# PMS.net
KiCad netlist of a schematic drawn in EAGLE
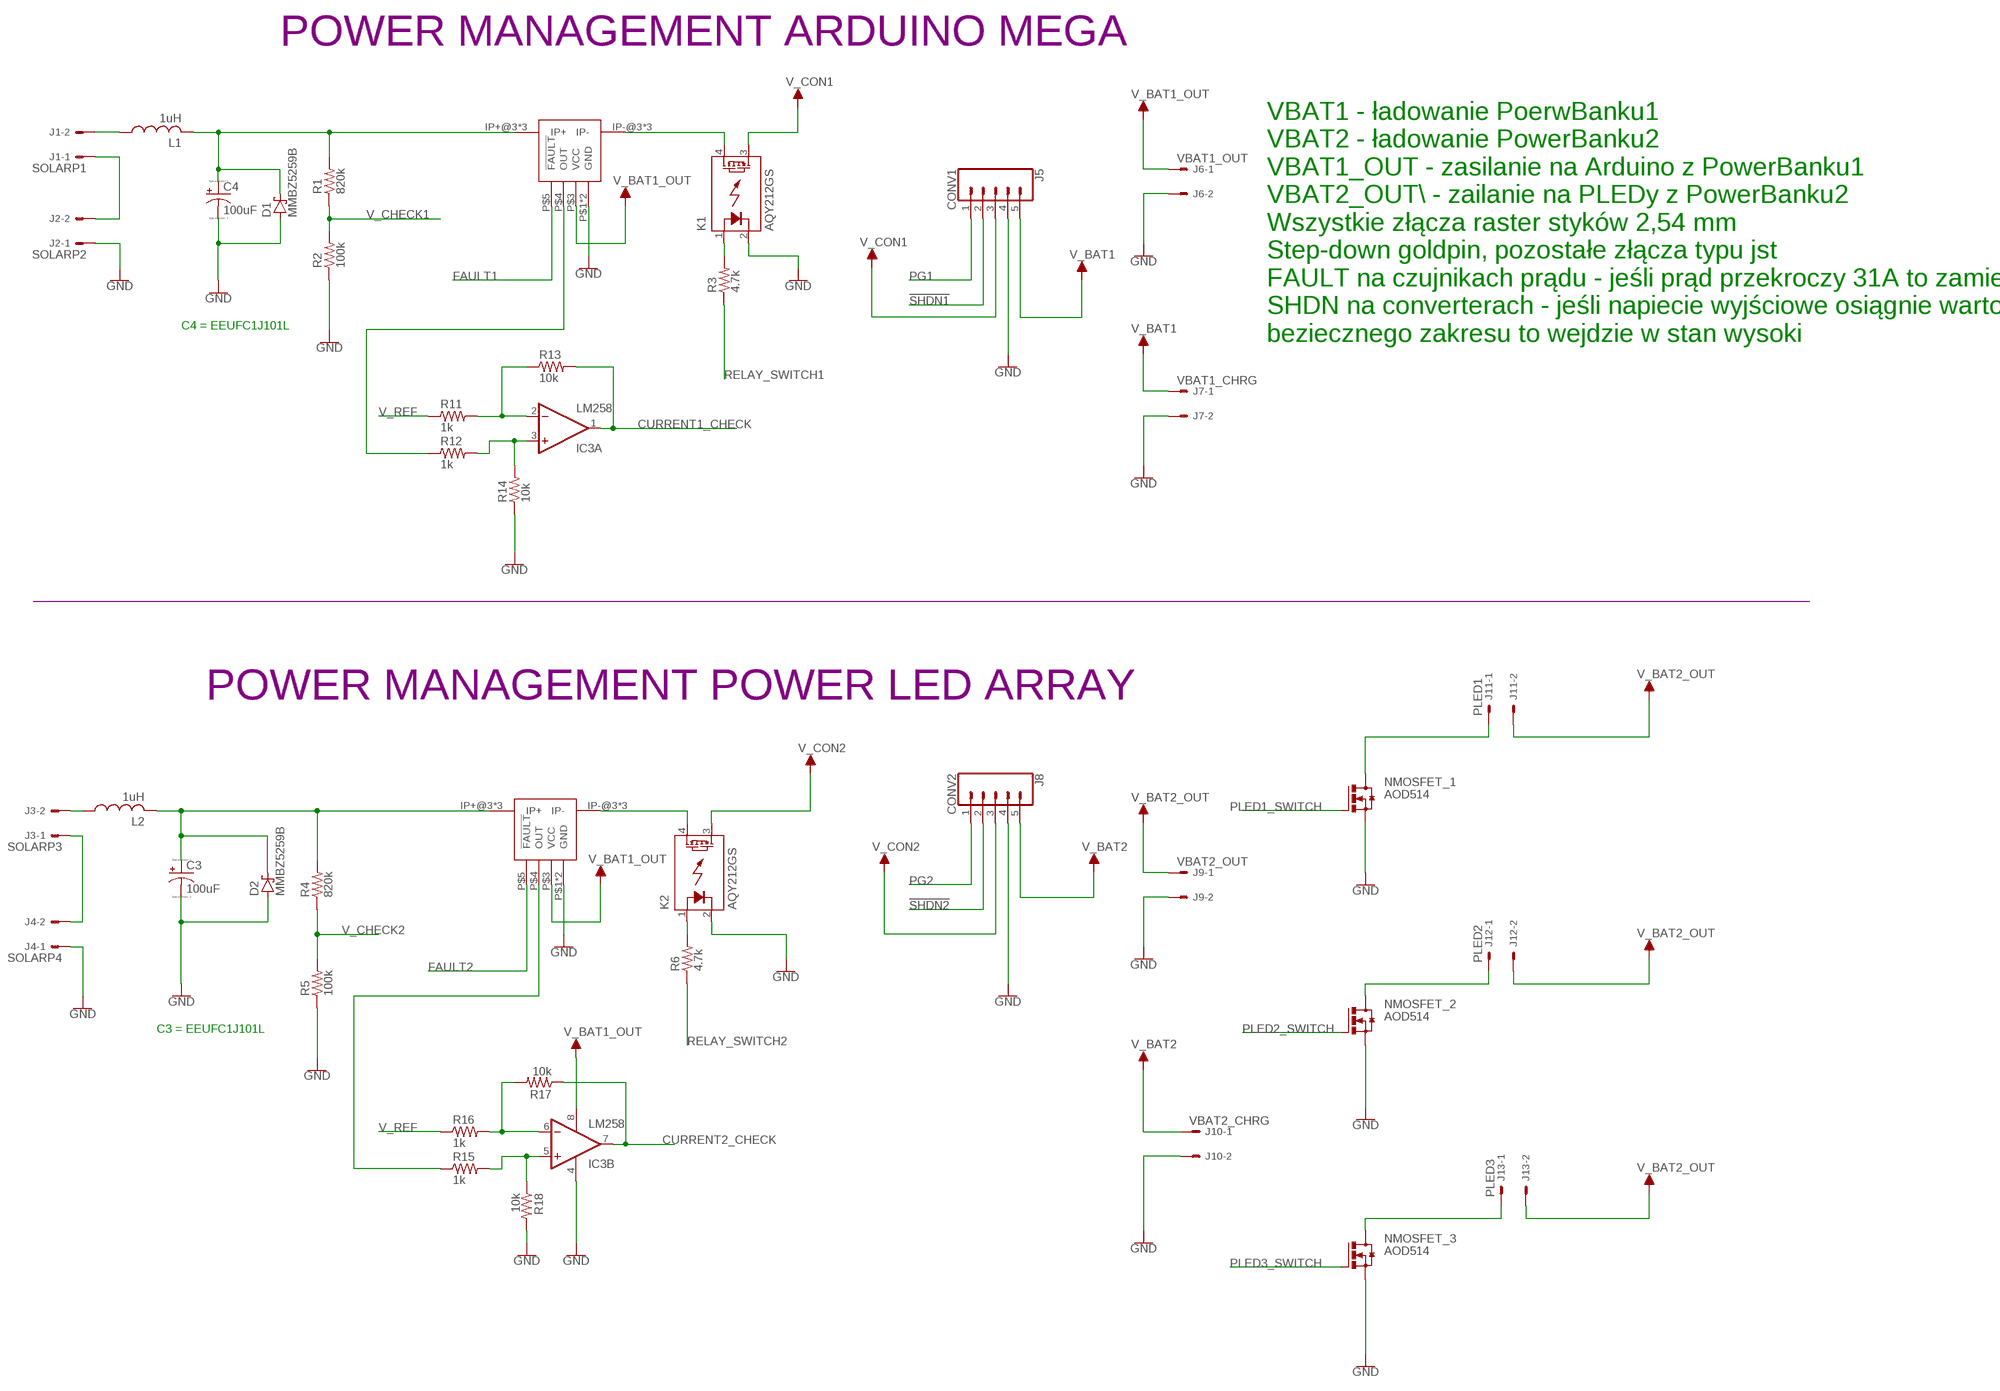
[diagram p0: schematic, sheet 1, part 1 of 2]
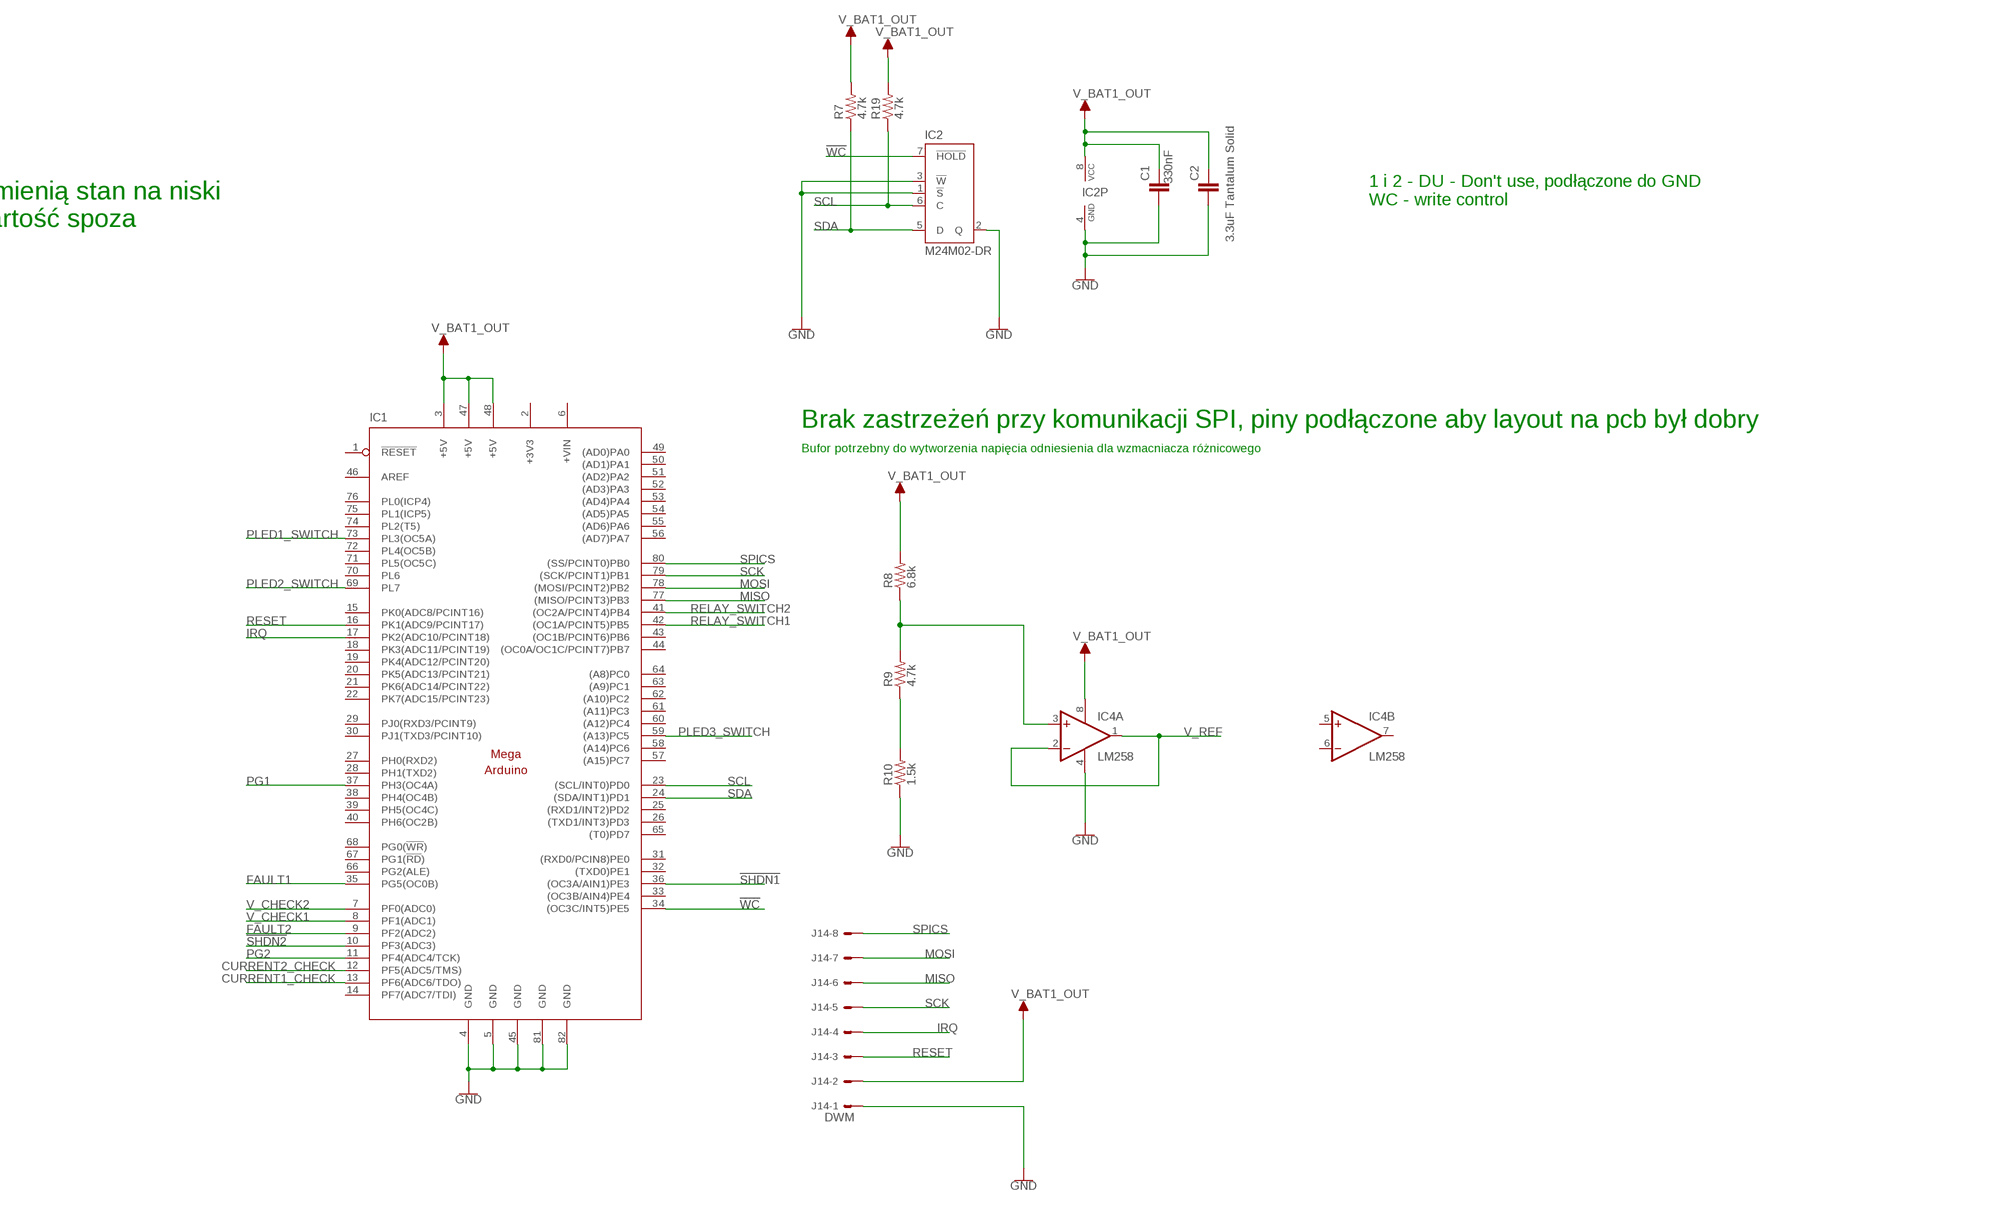
[diagram p1: schematic, sheet 1, part 2 of 2]

(export (version "E")
  (design (tool "Eeschema 10.0.6"))
  (components
    (comp (ref "C1")
      (value "330nF")
      (footprint "eagle-import:C0805")
      (libsource (lib "eagle-import") (part "C-EUC0805"))
    )
    (comp (ref "C2")
      (value "3.3uF Tantalum Solid")
      (footprint "eagle-import:C1206")
      (libsource (lib "eagle-import") (part "C-EUC1206"))
    )
    (comp (ref "C3")
      (value "100uF")
      (footprint "eagle-import:E3,5-8")
      (libsource (lib "eagle-import") (part "CPOL-USE3.5-8"))
    )
    (comp (ref "C4")
      (value "100uF")
      (footprint "eagle-import:E3,5-8")
      (libsource (lib "eagle-import") (part "CPOL-USE3.5-8"))
    )
    (comp (ref "CURRETN_SENS")
      (value "ACS711EXSH")
      (footprint "eagle-import:POLOLU2453_SMALL_HOLES")
      (libsource (lib "eagle-import") (part "ACS711EXSH"))
    )
    (comp (ref "D1")
      (value "MMBZ5259B")
      (footprint "eagle-import:SOT23")
      (libsource (lib "eagle-import") (part "BAS40"))
    )
    (comp (ref "D2")
      (value "MMBZ5259B")
      (footprint "eagle-import:SOT23")
      (libsource (lib "eagle-import") (part "BAS40"))
    )
    (comp (ref "IC1")
      (value "MEGAARDUINO_13")
      (footprint "eagle-import:MEGA_ARDUINO_3")
      (libsource (lib "eagle-import") (part "MEGAARDUINO_13"))
    )
    (comp (ref "IC2")
      (value "M24M02-DR")
      (footprint "eagle-import:SO08")
      (libsource (lib "eagle-import") (part "ST95P08M"))
    )
    (comp (ref "IC3")
      (value "LM258")
      (footprint "eagle-import:SO08")
      (libsource (lib "eagle-import") (part "LM358D"))
    )
    (comp (ref "IC4")
      (value "LM258")
      (footprint "eagle-import:SO08")
      (libsource (lib "eagle-import") (part "LM358D"))
    )
    (comp (ref "J1")
      (value "SOLARP1")
      (footprint "eagle-import:6410-02")
      (libsource (lib "eagle-import") (part "22-?-0227-2021"))
    )
    (comp (ref "J2")
      (value "SOLARP2")
      (footprint "eagle-import:6410-02")
      (libsource (lib "eagle-import") (part "22-?-0227-2021"))
    )
    (comp (ref "J3")
      (value "SOLARP3")
      (footprint "eagle-import:6410-02")
      (libsource (lib "eagle-import") (part "22-?-0227-2021"))
    )
    (comp (ref "J4")
      (value "SOLARP4")
      (footprint "eagle-import:6410-02")
      (libsource (lib "eagle-import") (part "22-?-0227-2021"))
    )
    (comp (ref "J5")
      (value "CONV1")
      (footprint "eagle-import:1X05")
      (libsource (lib "eagle-import") (part "CONN_05"))
    )
    (comp (ref "J6")
      (value "VBAT1_OUT")
      (footprint "eagle-import:6410-02")
      (libsource (lib "eagle-import") (part "22-?-0227-2021"))
    )
    (comp (ref "J7")
      (value "VBAT1_CHRG")
      (footprint "eagle-import:6410-02")
      (libsource (lib "eagle-import") (part "22-?-0227-2021"))
    )
    (comp (ref "J8")
      (value "CONV2")
      (footprint "eagle-import:1X05")
      (libsource (lib "eagle-import") (part "CONN_05"))
    )
    (comp (ref "J9")
      (value "VBAT2_OUT")
      (footprint "eagle-import:6410-02")
      (libsource (lib "eagle-import") (part "22-?-0227-2021"))
    )
    (comp (ref "J10")
      (value "VBAT2_CHRG")
      (footprint "eagle-import:6410-02")
      (libsource (lib "eagle-import") (part "22-?-0227-2021"))
    )
    (comp (ref "J11")
      (value "PLED1")
      (footprint "eagle-import:6410-02")
      (libsource (lib "eagle-import") (part "22-?-0227-2021"))
    )
    (comp (ref "J12")
      (value "PLED2")
      (footprint "eagle-import:6410-02")
      (libsource (lib "eagle-import") (part "22-?-0227-2021"))
    )
    (comp (ref "J13")
      (value "PLED3")
      (footprint "eagle-import:6410-02")
      (libsource (lib "eagle-import") (part "22-?-0227-2021"))
    )
    (comp (ref "J14")
      (value "DWM")
      (footprint "eagle-import:6410-08")
      (libsource (lib "eagle-import") (part "22-?-0827-2081"))
    )
    (comp (ref "K1")
      (value "AQY212GS")
      (footprint "eagle-import:SOP04")
      (libsource (lib "eagle-import") (part "AQYSOP21"))
    )
    (comp (ref "K2")
      (value "AQY212GS")
      (footprint "eagle-import:SOP04")
      (libsource (lib "eagle-import") (part "AQYSOP21"))
    )
    (comp (ref "L1")
      (value "1uH")
      (footprint "eagle-import:L3225M")
      (libsource (lib "eagle-import") (part "L-USL3225M"))
    )
    (comp (ref "L2")
      (value "1uH")
      (footprint "eagle-import:L3225M")
      (libsource (lib "eagle-import") (part "L-USL3225M"))
    )
    (comp (ref "NMOSFET_1")
      (value "AOD514")
      (footprint "eagle-import:TO252")
      (libsource (lib "eagle-import") (part "N_MOSFET_TO252"))
    )
    (comp (ref "NMOSFET_2")
      (value "AOD514")
      (footprint "eagle-import:TO252")
      (libsource (lib "eagle-import") (part "N_MOSFET_TO252"))
    )
    (comp (ref "NMOSFET_3")
      (value "AOD514")
      (footprint "eagle-import:TO252")
      (libsource (lib "eagle-import") (part "N_MOSFET_TO252"))
    )
    (comp (ref "R1")
      (value "820k")
      (footprint "eagle-import:R0805")
      (libsource (lib "eagle-import") (part "R-US_R0805"))
    )
    (comp (ref "R2")
      (value "100k")
      (footprint "eagle-import:R0805")
      (libsource (lib "eagle-import") (part "R-US_R0805"))
    )
    (comp (ref "R3")
      (value "4.7k")
      (footprint "eagle-import:R0805")
      (libsource (lib "eagle-import") (part "R-US_R0805"))
    )
    (comp (ref "R4")
      (value "820k")
      (footprint "eagle-import:R0805")
      (libsource (lib "eagle-import") (part "R-US_R0805"))
    )
    (comp (ref "R5")
      (value "100k")
      (footprint "eagle-import:R0805")
      (libsource (lib "eagle-import") (part "R-US_R0805"))
    )
    (comp (ref "R6")
      (value "4.7k")
      (footprint "eagle-import:R0805")
      (libsource (lib "eagle-import") (part "R-US_R0805"))
    )
    (comp (ref "R7")
      (value "4.7k")
      (footprint "eagle-import:R0805")
      (libsource (lib "eagle-import") (part "R-US_R0805"))
    )
    (comp (ref "R8")
      (value "6.8k")
      (footprint "eagle-import:R0805")
      (libsource (lib "eagle-import") (part "R-US_R0805"))
    )
    (comp (ref "R9")
      (value "4.7k")
      (footprint "eagle-import:R0805")
      (libsource (lib "eagle-import") (part "R-US_R0805"))
    )
    (comp (ref "R10")
      (value "1.5k")
      (footprint "eagle-import:R0805")
      (libsource (lib "eagle-import") (part "R-US_R0805"))
    )
    (comp (ref "R11")
      (value "1k")
      (footprint "eagle-import:R0805")
      (libsource (lib "eagle-import") (part "R-US_R0805"))
    )
    (comp (ref "R12")
      (value "1k")
      (footprint "eagle-import:R0805")
      (libsource (lib "eagle-import") (part "R-US_R0805"))
    )
    (comp (ref "R13")
      (value "10k")
      (footprint "eagle-import:R0805")
      (libsource (lib "eagle-import") (part "R-US_R0805"))
    )
    (comp (ref "R14")
      (value "10k")
      (footprint "eagle-import:R0805")
      (libsource (lib "eagle-import") (part "R-US_R0805"))
    )
    (comp (ref "R15")
      (value "1k")
      (footprint "eagle-import:R0805")
      (libsource (lib "eagle-import") (part "R-US_R0805"))
    )
    (comp (ref "R16")
      (value "1k")
      (footprint "eagle-import:R0805")
      (libsource (lib "eagle-import") (part "R-US_R0805"))
    )
    (comp (ref "R17")
      (value "10k")
      (footprint "eagle-import:R0805")
      (libsource (lib "eagle-import") (part "R-US_R0805"))
    )
    (comp (ref "R18")
      (value "10k")
      (footprint "eagle-import:R0805")
      (libsource (lib "eagle-import") (part "R-US_R0805"))
    )
    (comp (ref "R19")
      (value "4.7k")
      (footprint "eagle-import:R0805")
      (libsource (lib "eagle-import") (part "R-US_R0805"))
    )
    (comp (ref "U$2")
      (value "ACS711EXSH")
      (footprint "eagle-import:POLOLU2453_SMALL_HOLES")
      (libsource (lib "eagle-import") (part "ACS711EXSH"))
    )
  )
  (nets
    (net (code "1") (name "/+3V3") (class "Default")
      (node (ref "IC1") (pin "2") (pinfunction "+3V3_2") (pintype "power_in"))
    )
    (net (code "2") (name "/+VIN") (class "Default")
      (node (ref "IC1") (pin "6") (pinfunction "+VIN_6") (pintype "power_in"))
    )
    (net (code "3") (name "/CURRENT1_CHECK") (class "Default")
      (node (ref "IC1") (pin "13") (pinfunction "PF6(ADC6/TDO)_13") (pintype "bidirectional"))
      (node (ref "IC3") (pin "1") (pinfunction "OUT_1") (pintype "output"))
      (node (ref "R13") (pin "2") (pinfunction "2_2") (pintype "passive"))
    )
    (net (code "4") (name "/CURRENT2_CHECK") (class "Default")
      (node (ref "IC1") (pin "12") (pinfunction "PF5(ADC5/TMS)_12") (pintype "bidirectional"))
      (node (ref "IC3") (pin "7") (pinfunction "OUT_7") (pintype "output"))
      (node (ref "R17") (pin "1") (pinfunction "1_1") (pintype "passive"))
    )
    (net (code "5") (name "/FAULT1") (class "Default")
      (node (ref "CURRETN_SENS") (pin "P$5") (pinfunction "~{FAULT}_P$5") (pintype "bidirectional"))
      (node (ref "IC1") (pin "35") (pinfunction "PG5(OC0B)_35") (pintype "bidirectional"))
    )
    (net (code "6") (name "/FAULT2") (class "Default")
      (node (ref "IC1") (pin "9") (pinfunction "PF2(ADC2)_9") (pintype "bidirectional"))
      (node (ref "U$2") (pin "P$5") (pinfunction "~{FAULT}_P$5") (pintype "bidirectional"))
    )
    (net (code "7") (name "/IRQ") (class "Default")
      (node (ref "IC1") (pin "17") (pinfunction "PK2(ADC10/PCINT18)_17") (pintype "bidirectional"))
      (node (ref "J14") (pin "4") (pinfunction "S_4") (pintype "passive"))
    )
    (net (code "8") (name "/MISO") (class "Default")
      (node (ref "IC1") (pin "77") (pinfunction "(MISO/PCINT3)PB3_77") (pintype "bidirectional"))
      (node (ref "J14") (pin "6") (pinfunction "S_6") (pintype "passive"))
    )
    (net (code "9") (name "/MOSI") (class "Default")
      (node (ref "IC1") (pin "78") (pinfunction "(MOSI/PCINT2)PB2_78") (pintype "bidirectional"))
      (node (ref "J14") (pin "7") (pinfunction "S_7") (pintype "passive"))
    )
    (net (code "10") (name "/PG1") (class "Default")
      (node (ref "IC1") (pin "37") (pinfunction "PH3(OC4A)_37") (pintype "bidirectional"))
      (node (ref "J5") (pin "1") (pinfunction "1_1") (pintype "passive"))
    )
    (net (code "11") (name "/PG2") (class "Default")
      (node (ref "IC1") (pin "11") (pinfunction "PF4(ADC4/TCK)_11") (pintype "bidirectional"))
      (node (ref "J8") (pin "1") (pinfunction "1_1") (pintype "passive"))
    )
    (net (code "12") (name "/PLED1_SWITCH") (class "Default")
      (node (ref "IC1") (pin "73") (pinfunction "PL3(OC5A)_73") (pintype "bidirectional"))
      (node (ref "NMOSFET_1") (pin "1") (pinfunction "G_1") (pintype "passive"))
    )
    (net (code "13") (name "/PLED2_SWITCH") (class "Default")
      (node (ref "IC1") (pin "69") (pinfunction "PL7_69") (pintype "bidirectional"))
      (node (ref "NMOSFET_2") (pin "1") (pinfunction "G_1") (pintype "passive"))
    )
    (net (code "14") (name "/PLED3_SWITCH") (class "Default")
      (node (ref "IC1") (pin "59") (pinfunction "(A13)PC5_59") (pintype "bidirectional"))
      (node (ref "NMOSFET_3") (pin "1") (pinfunction "G_1") (pintype "passive"))
    )
    (net (code "15") (name "/RELAY_SWITCH1") (class "Default")
      (node (ref "IC1") (pin "42") (pinfunction "(OC1A/PCINT5)PB5_42") (pintype "bidirectional"))
      (node (ref "R3") (pin "1") (pinfunction "1_1") (pintype "passive"))
    )
    (net (code "16") (name "/RELAY_SWITCH2") (class "Default")
      (node (ref "IC1") (pin "41") (pinfunction "(OC2A/PCINT4)PB4_41") (pintype "bidirectional"))
      (node (ref "R6") (pin "1") (pinfunction "1_1") (pintype "passive"))
    )
    (net (code "17") (name "/RESET") (class "Default")
      (node (ref "IC1") (pin "16") (pinfunction "PK1(ADC9/PCINT17)_16") (pintype "bidirectional"))
      (node (ref "J14") (pin "3") (pinfunction "S_3") (pintype "passive"))
    )
    (net (code "18") (name "/SCK") (class "Default")
      (node (ref "IC1") (pin "79") (pinfunction "(SCK/PCINT1)PB1_79") (pintype "bidirectional"))
      (node (ref "J14") (pin "5") (pinfunction "S_5") (pintype "passive"))
    )
    (net (code "19") (name "/SCL") (class "Default")
      (node (ref "IC1") (pin "23") (pinfunction "(SCL/INT0)PD0_23") (pintype "bidirectional"))
      (node (ref "IC2") (pin "6") (pinfunction "C_6") (pintype "input"))
      (node (ref "R19") (pin "1") (pinfunction "1_1") (pintype "passive"))
    )
    (net (code "20") (name "/SDA") (class "Default")
      (node (ref "IC1") (pin "24") (pinfunction "(SDA/INT1)PD1_24") (pintype "bidirectional"))
      (node (ref "IC2") (pin "5") (pinfunction "D_5") (pintype "input"))
      (node (ref "R7") (pin "1") (pinfunction "1_1") (pintype "passive"))
    )
    (net (code "21") (name "/SPICS") (class "Default")
      (node (ref "IC1") (pin "80") (pinfunction "(SS/PCINT0)PB0_80") (pintype "bidirectional"))
      (node (ref "J14") (pin "8") (pinfunction "S_8") (pintype "passive"))
    )
    (net (code "22") (name "/V_CHECK1") (class "Default")
      (node (ref "IC1") (pin "8") (pinfunction "PF1(ADC1)_8") (pintype "bidirectional"))
      (node (ref "R1") (pin "1") (pinfunction "1_1") (pintype "passive"))
      (node (ref "R2") (pin "2") (pinfunction "2_2") (pintype "passive"))
    )
    (net (code "23") (name "/V_CHECK2") (class "Default")
      (node (ref "IC1") (pin "7") (pinfunction "PF0(ADC0)_7") (pintype "bidirectional"))
      (node (ref "R4") (pin "1") (pinfunction "1_1") (pintype "passive"))
      (node (ref "R5") (pin "2") (pinfunction "2_2") (pintype "passive"))
    )
    (net (code "24") (name "/V_REF") (class "Default")
      (node (ref "IC4") (pin "1") (pinfunction "OUT_1") (pintype "output"))
      (node (ref "IC4") (pin "2") (pinfunction "-IN_2") (pintype "input"))
      (node (ref "R11") (pin "1") (pinfunction "1_1") (pintype "passive"))
      (node (ref "R16") (pin "1") (pinfunction "1_1") (pintype "passive"))
    )
    (net (code "25") (name "/~{SHDN1}") (class "Default")
      (node (ref "IC1") (pin "36") (pinfunction "(OC3A/AIN1)PE3_36") (pintype "bidirectional"))
      (node (ref "J5") (pin "2") (pinfunction "2_2") (pintype "passive"))
    )
    (net (code "26") (name "/~{SHDN2}") (class "Default")
      (node (ref "IC1") (pin "10") (pinfunction "PF3(ADC3)_10") (pintype "bidirectional"))
      (node (ref "J8") (pin "2") (pinfunction "2_2") (pintype "passive"))
    )
    (net (code "27") (name "/~{WC}") (class "Default")
      (node (ref "IC1") (pin "34") (pinfunction "(OC3C/INT5)PE5_34") (pintype "bidirectional"))
      (node (ref "IC2") (pin "7") (pinfunction "~{HOLD}_7") (pintype "input"))
    )
    (net (code "28") (name "GND") (class "Default")
      (node (ref "C1") (pin "1") (pinfunction "1_1") (pintype "passive"))
      (node (ref "C2") (pin "1") (pinfunction "1_1") (pintype "passive"))
      (node (ref "C3") (pin "-") (pinfunction "-_-") (pintype "passive"))
      (node (ref "C4") (pin "-") (pinfunction "-_-") (pintype "passive"))
      (node (ref "CURRETN_SENS") (pin "P$1") (pinfunction "GND_P$1") (pintype "bidirectional"))
      (node (ref "CURRETN_SENS") (pin "P$2") (pinfunction "GND_P$2") (pintype "bidirectional"))
      (node (ref "D1") (pin "1") (pinfunction "A_1") (pintype "passive"))
      (node (ref "D2") (pin "1") (pinfunction "A_1") (pintype "passive"))
      (node (ref "IC1") (pin "4") (pinfunction "GND_4") (pintype "power_in"))
      (node (ref "IC1") (pin "45") (pinfunction "GND_45") (pintype "power_in"))
      (node (ref "IC1") (pin "5") (pinfunction "GND_5") (pintype "power_in"))
      (node (ref "IC1") (pin "81") (pinfunction "GND_81") (pintype "power_in"))
      (node (ref "IC1") (pin "82") (pinfunction "GND_82") (pintype "power_in"))
      (node (ref "IC2") (pin "1") (pinfunction "~{S}_1") (pintype "input"))
      (node (ref "IC2") (pin "2") (pinfunction "Q_2") (pintype "tri_state"))
      (node (ref "IC2") (pin "3") (pinfunction "~{W}_3") (pintype "input"))
      (node (ref "IC2") (pin "4") (pinfunction "GND_4") (pintype "power_in"))
      (node (ref "IC3") (pin "4") (pinfunction "V-_4") (pintype "power_in"))
      (node (ref "IC4") (pin "4") (pinfunction "V-_4") (pintype "power_in"))
      (node (ref "J10") (pin "2") (pinfunction "S_2") (pintype "passive"))
      (node (ref "J14") (pin "1") (pinfunction "S_1") (pintype "passive"))
      (node (ref "J2") (pin "1") (pinfunction "S_1") (pintype "passive"))
      (node (ref "J4") (pin "1") (pinfunction "S_1") (pintype "passive"))
      (node (ref "J5") (pin "4") (pinfunction "4_4") (pintype "passive"))
      (node (ref "J6") (pin "2") (pinfunction "S_2") (pintype "passive"))
      (node (ref "J7") (pin "2") (pinfunction "S_2") (pintype "passive"))
      (node (ref "J8") (pin "4") (pinfunction "4_4") (pintype "passive"))
      (node (ref "J9") (pin "2") (pinfunction "S_2") (pintype "passive"))
      (node (ref "K1") (pin "2") (pinfunction "K_2") (pintype "passive"))
      (node (ref "K2") (pin "2") (pinfunction "K_2") (pintype "passive"))
      (node (ref "NMOSFET_1") (pin "3") (pinfunction "S_3") (pintype "passive"))
      (node (ref "NMOSFET_2") (pin "3") (pinfunction "S_3") (pintype "passive"))
      (node (ref "NMOSFET_3") (pin "3") (pinfunction "S_3") (pintype "passive"))
      (node (ref "R10") (pin "1") (pinfunction "1_1") (pintype "passive"))
      (node (ref "R14") (pin "1") (pinfunction "1_1") (pintype "passive"))
      (node (ref "R18") (pin "2") (pinfunction "2_2") (pintype "passive"))
      (node (ref "R2") (pin "1") (pinfunction "1_1") (pintype "passive"))
      (node (ref "R5") (pin "1") (pinfunction "1_1") (pintype "passive"))
      (node (ref "U$2") (pin "P$1") (pinfunction "GND_P$1") (pintype "bidirectional"))
      (node (ref "U$2") (pin "P$2") (pinfunction "GND_P$2") (pintype "bidirectional"))
    )
    (net (code "29") (name "Net-(CURRETN_SENS-OUT)") (class "Default")
      (node (ref "CURRETN_SENS") (pin "P$4") (pinfunction "OUT_P$4") (pintype "bidirectional"))
      (node (ref "R12") (pin "1") (pinfunction "1_1") (pintype "passive"))
    )
    (net (code "30") (name "Net-(D1-C)") (class "Default")
      (node (ref "C4") (pin "+") (pinfunction "+_+") (pintype "passive"))
      (node (ref "CURRETN_SENS") (pin "IP+@3") (pinfunction "IP+_IP+@3") (pintype "bidirectional"))
      (node (ref "CURRETN_SENS") (pin "IP+@4") (pinfunction "IP+_IP+@4") (pintype "bidirectional"))
      (node (ref "CURRETN_SENS") (pin "IP+@5") (pinfunction "IP+_IP+@5") (pintype "bidirectional"))
      (node (ref "D1") (pin "3") (pinfunction "C_3") (pintype "passive"))
      (node (ref "L1") (pin "2") (pinfunction "2_2") (pintype "passive"))
      (node (ref "R1") (pin "2") (pinfunction "2_2") (pintype "passive"))
    )
    (net (code "31") (name "Net-(D2-C)") (class "Default")
      (node (ref "C3") (pin "+") (pinfunction "+_+") (pintype "passive"))
      (node (ref "D2") (pin "3") (pinfunction "C_3") (pintype "passive"))
      (node (ref "L2") (pin "2") (pinfunction "2_2") (pintype "passive"))
      (node (ref "R4") (pin "2") (pinfunction "2_2") (pintype "passive"))
      (node (ref "U$2") (pin "IP+@3") (pinfunction "IP+_IP+@3") (pintype "bidirectional"))
      (node (ref "U$2") (pin "IP+@4") (pinfunction "IP+_IP+@4") (pintype "bidirectional"))
      (node (ref "U$2") (pin "IP+@5") (pinfunction "IP+_IP+@5") (pintype "bidirectional"))
    )
    (net (code "32") (name "Net-(IC3A-+IN)") (class "Default")
      (node (ref "IC3") (pin "3") (pinfunction "+IN_3") (pintype "input"))
      (node (ref "R12") (pin "2") (pinfunction "2_2") (pintype "passive"))
      (node (ref "R14") (pin "2") (pinfunction "2_2") (pintype "passive"))
    )
    (net (code "33") (name "Net-(IC3A--IN)") (class "Default")
      (node (ref "IC3") (pin "2") (pinfunction "-IN_2") (pintype "input"))
      (node (ref "R11") (pin "2") (pinfunction "2_2") (pintype "passive"))
      (node (ref "R13") (pin "1") (pinfunction "1_1") (pintype "passive"))
    )
    (net (code "34") (name "Net-(IC3B-+IN)") (class "Default")
      (node (ref "IC3") (pin "5") (pinfunction "+IN_5") (pintype "input"))
      (node (ref "R15") (pin "2") (pinfunction "2_2") (pintype "passive"))
      (node (ref "R18") (pin "1") (pinfunction "1_1") (pintype "passive"))
    )
    (net (code "35") (name "Net-(IC3B--IN)") (class "Default")
      (node (ref "IC3") (pin "6") (pinfunction "-IN_6") (pintype "input"))
      (node (ref "R16") (pin "2") (pinfunction "2_2") (pintype "passive"))
      (node (ref "R17") (pin "2") (pinfunction "2_2") (pintype "passive"))
    )
    (net (code "36") (name "Net-(IC4A-+IN)") (class "Default")
      (node (ref "IC4") (pin "3") (pinfunction "+IN_3") (pintype "input"))
      (node (ref "R8") (pin "1") (pinfunction "1_1") (pintype "passive"))
      (node (ref "R9") (pin "2") (pinfunction "2_2") (pintype "passive"))
    )
    (net (code "37") (name "Net-(J1A-S)") (class "Default")
      (node (ref "J1") (pin "1") (pinfunction "S_1") (pintype "passive"))
      (node (ref "J2") (pin "2") (pinfunction "S_2") (pintype "passive"))
    )
    (net (code "38") (name "Net-(J1B-S)") (class "Default")
      (node (ref "J1") (pin "2") (pinfunction "S_2") (pintype "passive"))
      (node (ref "L1") (pin "1") (pinfunction "1_1") (pintype "passive"))
    )
    (net (code "39") (name "Net-(J3A-S)") (class "Default")
      (node (ref "J3") (pin "1") (pinfunction "S_1") (pintype "passive"))
      (node (ref "J4") (pin "2") (pinfunction "S_2") (pintype "passive"))
    )
    (net (code "40") (name "Net-(J3B-S)") (class "Default")
      (node (ref "J3") (pin "2") (pinfunction "S_2") (pintype "passive"))
      (node (ref "L2") (pin "1") (pinfunction "1_1") (pintype "passive"))
    )
    (net (code "41") (name "Net-(J11A-S)") (class "Default")
      (node (ref "J11") (pin "1") (pinfunction "S_1") (pintype "passive"))
      (node (ref "NMOSFET_1") (pin "4") (pinfunction "D_4") (pintype "passive"))
    )
    (net (code "42") (name "Net-(J12A-S)") (class "Default")
      (node (ref "J12") (pin "1") (pinfunction "S_1") (pintype "passive"))
      (node (ref "NMOSFET_2") (pin "4") (pinfunction "D_4") (pintype "passive"))
    )
    (net (code "43") (name "Net-(J13A-S)") (class "Default")
      (node (ref "J13") (pin "1") (pinfunction "S_1") (pintype "passive"))
      (node (ref "NMOSFET_3") (pin "4") (pinfunction "D_4") (pintype "passive"))
    )
    (net (code "44") (name "Net-(K1-A)") (class "Default")
      (node (ref "K1") (pin "1") (pinfunction "A_1") (pintype "passive"))
      (node (ref "R3") (pin "2") (pinfunction "2_2") (pintype "passive"))
    )
    (net (code "45") (name "Net-(K1-DS1)") (class "Default")
      (node (ref "CURRETN_SENS") (pin "IP-@3") (pinfunction "IP-_IP-@3") (pintype "bidirectional"))
      (node (ref "CURRETN_SENS") (pin "IP-@4") (pinfunction "IP-_IP-@4") (pintype "bidirectional"))
      (node (ref "CURRETN_SENS") (pin "IP-@5") (pinfunction "IP-_IP-@5") (pintype "bidirectional"))
      (node (ref "K1") (pin "4") (pinfunction "DS1_4") (pintype "passive"))
    )
    (net (code "46") (name "Net-(K2-A)") (class "Default")
      (node (ref "K2") (pin "1") (pinfunction "A_1") (pintype "passive"))
      (node (ref "R6") (pin "2") (pinfunction "2_2") (pintype "passive"))
    )
    (net (code "47") (name "Net-(K2-DS1)") (class "Default")
      (node (ref "K2") (pin "4") (pinfunction "DS1_4") (pintype "passive"))
      (node (ref "U$2") (pin "IP-@3") (pinfunction "IP-_IP-@3") (pintype "bidirectional"))
      (node (ref "U$2") (pin "IP-@4") (pinfunction "IP-_IP-@4") (pintype "bidirectional"))
      (node (ref "U$2") (pin "IP-@5") (pinfunction "IP-_IP-@5") (pintype "bidirectional"))
    )
    (net (code "48") (name "Net-(R10-Pad2)") (class "Default")
      (node (ref "R10") (pin "2") (pinfunction "2_2") (pintype "passive"))
      (node (ref "R9") (pin "1") (pinfunction "1_1") (pintype "passive"))
    )
    (net (code "49") (name "Net-(U$2-OUT)") (class "Default")
      (node (ref "R15") (pin "1") (pinfunction "1_1") (pintype "passive"))
      (node (ref "U$2") (pin "P$4") (pinfunction "OUT_P$4") (pintype "bidirectional"))
    )
    (net (code "50") (name "V_BAT1") (class "Default")
      (node (ref "J5") (pin "5") (pinfunction "5_5") (pintype "passive"))
      (node (ref "J7") (pin "1") (pinfunction "S_1") (pintype "passive"))
    )
    (net (code "51") (name "V_BAT1_OUT") (class "Default")
      (node (ref "C1") (pin "2") (pinfunction "2_2") (pintype "passive"))
      (node (ref "C2") (pin "2") (pinfunction "2_2") (pintype "passive"))
      (node (ref "CURRETN_SENS") (pin "P$3") (pinfunction "VCC_P$3") (pintype "bidirectional"))
      (node (ref "IC1") (pin "3") (pinfunction "+5V_3") (pintype "power_in"))
      (node (ref "IC1") (pin "47") (pinfunction "+5V_47") (pintype "power_in"))
      (node (ref "IC1") (pin "48") (pinfunction "+5V_48") (pintype "power_in"))
      (node (ref "IC2") (pin "8") (pinfunction "VCC_8") (pintype "power_in"))
      (node (ref "IC3") (pin "8") (pinfunction "V+_8") (pintype "power_in"))
      (node (ref "IC4") (pin "8") (pinfunction "V+_8") (pintype "power_in"))
      (node (ref "J14") (pin "2") (pinfunction "S_2") (pintype "passive"))
      (node (ref "J6") (pin "1") (pinfunction "S_1") (pintype "passive"))
      (node (ref "R19") (pin "2") (pinfunction "2_2") (pintype "passive"))
      (node (ref "R7") (pin "2") (pinfunction "2_2") (pintype "passive"))
      (node (ref "R8") (pin "2") (pinfunction "2_2") (pintype "passive"))
      (node (ref "U$2") (pin "P$3") (pinfunction "VCC_P$3") (pintype "bidirectional"))
    )
    (net (code "52") (name "V_BAT2") (class "Default")
      (node (ref "J10") (pin "1") (pinfunction "S_1") (pintype "passive"))
      (node (ref "J8") (pin "5") (pinfunction "5_5") (pintype "passive"))
    )
    (net (code "53") (name "V_BAT2_OUT") (class "Default")
      (node (ref "J11") (pin "2") (pinfunction "S_2") (pintype "passive"))
      (node (ref "J12") (pin "2") (pinfunction "S_2") (pintype "passive"))
      (node (ref "J13") (pin "2") (pinfunction "S_2") (pintype "passive"))
      (node (ref "J9") (pin "1") (pinfunction "S_1") (pintype "passive"))
    )
    (net (code "54") (name "V_CON1") (class "Default")
      (node (ref "J5") (pin "3") (pinfunction "3_3") (pintype "passive"))
      (node (ref "K1") (pin "3") (pinfunction "DS2_3") (pintype "passive"))
    )
    (net (code "55") (name "V_CON2") (class "Default")
      (node (ref "J8") (pin "3") (pinfunction "3_3") (pintype "passive"))
      (node (ref "K2") (pin "3") (pinfunction "DS2_3") (pintype "passive"))
    )
    (net (code "56") (name "unconnected-(IC1-(A8)PC0-Pad64)") (class "Default")
      (node (ref "IC1") (pin "64") (pinfunction "(A8)PC0_64") (pintype "bidirectional"))
    )
    (net (code "57") (name "unconnected-(IC1-(A9)PC1-Pad63)") (class "Default")
      (node (ref "IC1") (pin "63") (pinfunction "(A9)PC1_63") (pintype "bidirectional"))
    )
    (net (code "58") (name "unconnected-(IC1-(A10)PC2-Pad62)") (class "Default")
      (node (ref "IC1") (pin "62") (pinfunction "(A10)PC2_62") (pintype "bidirectional"))
    )
    (net (code "59") (name "unconnected-(IC1-(A11)PC3-Pad61)") (class "Default")
      (node (ref "IC1") (pin "61") (pinfunction "(A11)PC3_61") (pintype "bidirectional"))
    )
    (net (code "60") (name "unconnected-(IC1-(A12)PC4-Pad60)") (class "Default")
      (node (ref "IC1") (pin "60") (pinfunction "(A12)PC4_60") (pintype "bidirectional"))
    )
    (net (code "61") (name "unconnected-(IC1-(A14)PC6-Pad58)") (class "Default")
      (node (ref "IC1") (pin "58") (pinfunction "(A14)PC6_58") (pintype "bidirectional"))
    )
    (net (code "62") (name "unconnected-(IC1-(A15)PC7-Pad57)") (class "Default")
      (node (ref "IC1") (pin "57") (pinfunction "(A15)PC7_57") (pintype "bidirectional"))
    )
    (net (code "63") (name "unconnected-(IC1-(AD0)PA0-Pad49)") (class "Default")
      (node (ref "IC1") (pin "49") (pinfunction "(AD0)PA0_49") (pintype "bidirectional"))
    )
    (net (code "64") (name "unconnected-(IC1-(AD1)PA1-Pad50)") (class "Default")
      (node (ref "IC1") (pin "50") (pinfunction "(AD1)PA1_50") (pintype "bidirectional"))
    )
    (net (code "65") (name "unconnected-(IC1-(AD2)PA2-Pad51)") (class "Default")
      (node (ref "IC1") (pin "51") (pinfunction "(AD2)PA2_51") (pintype "bidirectional"))
    )
    (net (code "66") (name "unconnected-(IC1-(AD3)PA3-Pad52)") (class "Default")
      (node (ref "IC1") (pin "52") (pinfunction "(AD3)PA3_52") (pintype "bidirectional"))
    )
    (net (code "67") (name "unconnected-(IC1-(AD4)PA4-Pad53)") (class "Default")
      (node (ref "IC1") (pin "53") (pinfunction "(AD4)PA4_53") (pintype "bidirectional"))
    )
    (net (code "68") (name "unconnected-(IC1-(AD5)PA5-Pad54)") (class "Default")
      (node (ref "IC1") (pin "54") (pinfunction "(AD5)PA5_54") (pintype "bidirectional"))
    )
    (net (code "69") (name "unconnected-(IC1-(AD6)PA6-Pad55)") (class "Default")
      (node (ref "IC1") (pin "55") (pinfunction "(AD6)PA6_55") (pintype "bidirectional"))
    )
    (net (code "70") (name "unconnected-(IC1-(AD7)PA7-Pad56)") (class "Default")
      (node (ref "IC1") (pin "56") (pinfunction "(AD7)PA7_56") (pintype "bidirectional"))
    )
    (net (code "71") (name "unconnected-(IC1-(OC0A{slash}OC1C{slash}PCINT7)PB7-Pad44)") (class "Default")
      (node (ref "IC1") (pin "44") (pinfunction "(OC0A/OC1C/PCINT7)PB7_44") (pintype "bidirectional"))
    )
    (net (code "72") (name "unconnected-(IC1-(OC1B{slash}PCINT6)PB6-Pad43)") (class "Default")
      (node (ref "IC1") (pin "43") (pinfunction "(OC1B/PCINT6)PB6_43") (pintype "bidirectional"))
    )
    (net (code "73") (name "unconnected-(IC1-(OC3B{slash}AIN4)PE4-Pad33)") (class "Default")
      (node (ref "IC1") (pin "33") (pinfunction "(OC3B/AIN4)PE4_33") (pintype "bidirectional"))
    )
    (net (code "74") (name "unconnected-(IC1-(RXD0{slash}PCIN8)PE0-Pad31)") (class "Default")
      (node (ref "IC1") (pin "31") (pinfunction "(RXD0/PCIN8)PE0_31") (pintype "bidirectional"))
    )
    (net (code "75") (name "unconnected-(IC1-(RXD1{slash}INT2)PD2-Pad25)") (class "Default")
      (node (ref "IC1") (pin "25") (pinfunction "(RXD1/INT2)PD2_25") (pintype "bidirectional"))
    )
    (net (code "76") (name "unconnected-(IC1-(T0)PD7-Pad65)") (class "Default")
      (node (ref "IC1") (pin "65") (pinfunction "(T0)PD7_65") (pintype "bidirectional"))
    )
    (net (code "77") (name "unconnected-(IC1-(TXD0)PE1-Pad32)") (class "Default")
      (node (ref "IC1") (pin "32") (pinfunction "(TXD0)PE1_32") (pintype "bidirectional"))
    )
    (net (code "78") (name "unconnected-(IC1-(TXD1{slash}INT3)PD3-Pad26)") (class "Default")
      (node (ref "IC1") (pin "26") (pinfunction "(TXD1/INT3)PD3_26") (pintype "bidirectional"))
    )
    (net (code "79") (name "unconnected-(IC1-AREF-Pad46)") (class "Default")
      (node (ref "IC1") (pin "46") (pinfunction "AREF_46") (pintype "bidirectional"))
    )
    (net (code "80") (name "unconnected-(IC1-PF7(ADC7{slash}TDI)-Pad14)") (class "Default")
      (node (ref "IC1") (pin "14") (pinfunction "PF7(ADC7/TDI)_14") (pintype "bidirectional"))
    )
    (net (code "81") (name "unconnected-(IC1-PG0(~{WR})-Pad68)") (class "Default")
      (node (ref "IC1") (pin "68") (pinfunction "PG0(~{WR})_68") (pintype "bidirectional"))
    )
    (net (code "82") (name "unconnected-(IC1-PG1(~{RD})-Pad67)") (class "Default")
      (node (ref "IC1") (pin "67") (pinfunction "PG1(~{RD})_67") (pintype "bidirectional"))
    )
    (net (code "83") (name "unconnected-(IC1-PG2(ALE)-Pad66)") (class "Default")
      (node (ref "IC1") (pin "66") (pinfunction "PG2(ALE)_66") (pintype "bidirectional"))
    )
    (net (code "84") (name "unconnected-(IC1-PH0(RXD2)-Pad27)") (class "Default")
      (node (ref "IC1") (pin "27") (pinfunction "PH0(RXD2)_27") (pintype "bidirectional"))
    )
    (net (code "85") (name "unconnected-(IC1-PH1(TXD2)-Pad28)") (class "Default")
      (node (ref "IC1") (pin "28") (pinfunction "PH1(TXD2)_28") (pintype "bidirectional"))
    )
    (net (code "86") (name "unconnected-(IC1-PH4(OC4B)-Pad38)") (class "Default")
      (node (ref "IC1") (pin "38") (pinfunction "PH4(OC4B)_38") (pintype "bidirectional"))
    )
    (net (code "87") (name "unconnected-(IC1-PH5(OC4C)-Pad39)") (class "Default")
      (node (ref "IC1") (pin "39") (pinfunction "PH5(OC4C)_39") (pintype "bidirectional"))
    )
    (net (code "88") (name "unconnected-(IC1-PH6(OC2B)-Pad40)") (class "Default")
      (node (ref "IC1") (pin "40") (pinfunction "PH6(OC2B)_40") (pintype "bidirectional"))
    )
    (net (code "89") (name "unconnected-(IC1-PJ0(RXD3{slash}PCINT9)-Pad29)") (class "Default")
      (node (ref "IC1") (pin "29") (pinfunction "PJ0(RXD3/PCINT9)_29") (pintype "bidirectional"))
    )
    (net (code "90") (name "unconnected-(IC1-PJ1(TXD3{slash}PCINT10)-Pad30)") (class "Default")
      (node (ref "IC1") (pin "30") (pinfunction "PJ1(TXD3/PCINT10)_30") (pintype "bidirectional"))
    )
    (net (code "91") (name "unconnected-(IC1-PK0(ADC8{slash}PCINT16)-Pad15)") (class "Default")
      (node (ref "IC1") (pin "15") (pinfunction "PK0(ADC8/PCINT16)_15") (pintype "bidirectional"))
    )
    (net (code "92") (name "unconnected-(IC1-PK3(ADC11{slash}PCINT19)-Pad18)") (class "Default")
      (node (ref "IC1") (pin "18") (pinfunction "PK3(ADC11/PCINT19)_18") (pintype "bidirectional"))
    )
    (net (code "93") (name "unconnected-(IC1-PK4(ADC12{slash}PCINT20)-Pad19)") (class "Default")
      (node (ref "IC1") (pin "19") (pinfunction "PK4(ADC12/PCINT20)_19") (pintype "bidirectional"))
    )
    (net (code "94") (name "unconnected-(IC1-PK5(ADC13{slash}PCINT21)-Pad20)") (class "Default")
      (node (ref "IC1") (pin "20") (pinfunction "PK5(ADC13/PCINT21)_20") (pintype "bidirectional"))
    )
    (net (code "95") (name "unconnected-(IC1-PK6(ADC14{slash}PCINT22)-Pad21)") (class "Default")
      (node (ref "IC1") (pin "21") (pinfunction "PK6(ADC14/PCINT22)_21") (pintype "bidirectional"))
    )
    (net (code "96") (name "unconnected-(IC1-PK7(ADC15{slash}PCINT23)-Pad22)") (class "Default")
      (node (ref "IC1") (pin "22") (pinfunction "PK7(ADC15/PCINT23)_22") (pintype "bidirectional"))
    )
    (net (code "97") (name "unconnected-(IC1-PL0(ICP4)-Pad76)") (class "Default")
      (node (ref "IC1") (pin "76") (pinfunction "PL0(ICP4)_76") (pintype "bidirectional"))
    )
    (net (code "98") (name "unconnected-(IC1-PL1(ICP5)-Pad75)") (class "Default")
      (node (ref "IC1") (pin "75") (pinfunction "PL1(ICP5)_75") (pintype "bidirectional"))
    )
    (net (code "99") (name "unconnected-(IC1-PL2(T5)-Pad74)") (class "Default")
      (node (ref "IC1") (pin "74") (pinfunction "PL2(T5)_74") (pintype "bidirectional"))
    )
    (net (code "100") (name "unconnected-(IC1-PL4(OC5B)-Pad72)") (class "Default")
      (node (ref "IC1") (pin "72") (pinfunction "PL4(OC5B)_72") (pintype "bidirectional"))
    )
    (net (code "101") (name "unconnected-(IC1-PL5(OC5C)-Pad71)") (class "Default")
      (node (ref "IC1") (pin "71") (pinfunction "PL5(OC5C)_71") (pintype "bidirectional"))
    )
    (net (code "102") (name "unconnected-(IC1-PL6-Pad70)") (class "Default")
      (node (ref "IC1") (pin "70") (pinfunction "PL6_70") (pintype "bidirectional"))
    )
    (net (code "103") (name "unconnected-(IC1-~{RESET}-Pad1)") (class "Default")
      (node (ref "IC1") (pin "1") (pinfunction "~{RESET}_1") (pintype "bidirectional"))
    )
    (net (code "104") (name "unconnected-(IC4B-+IN-Pad5)") (class "Default")
      (node (ref "IC4") (pin "5") (pinfunction "+IN_5") (pintype "input"))
    )
    (net (code "105") (name "unconnected-(IC4B--IN-Pad6)") (class "Default")
      (node (ref "IC4") (pin "6") (pinfunction "-IN_6") (pintype "input"))
    )
    (net (code "106") (name "unconnected-(IC4B-OUT-Pad7)") (class "Default")
      (node (ref "IC4") (pin "7") (pinfunction "OUT_7") (pintype "output"))
    )
  )
)
